# RADIO.net
KiCad netlist of a schematic drawn in EAGLE
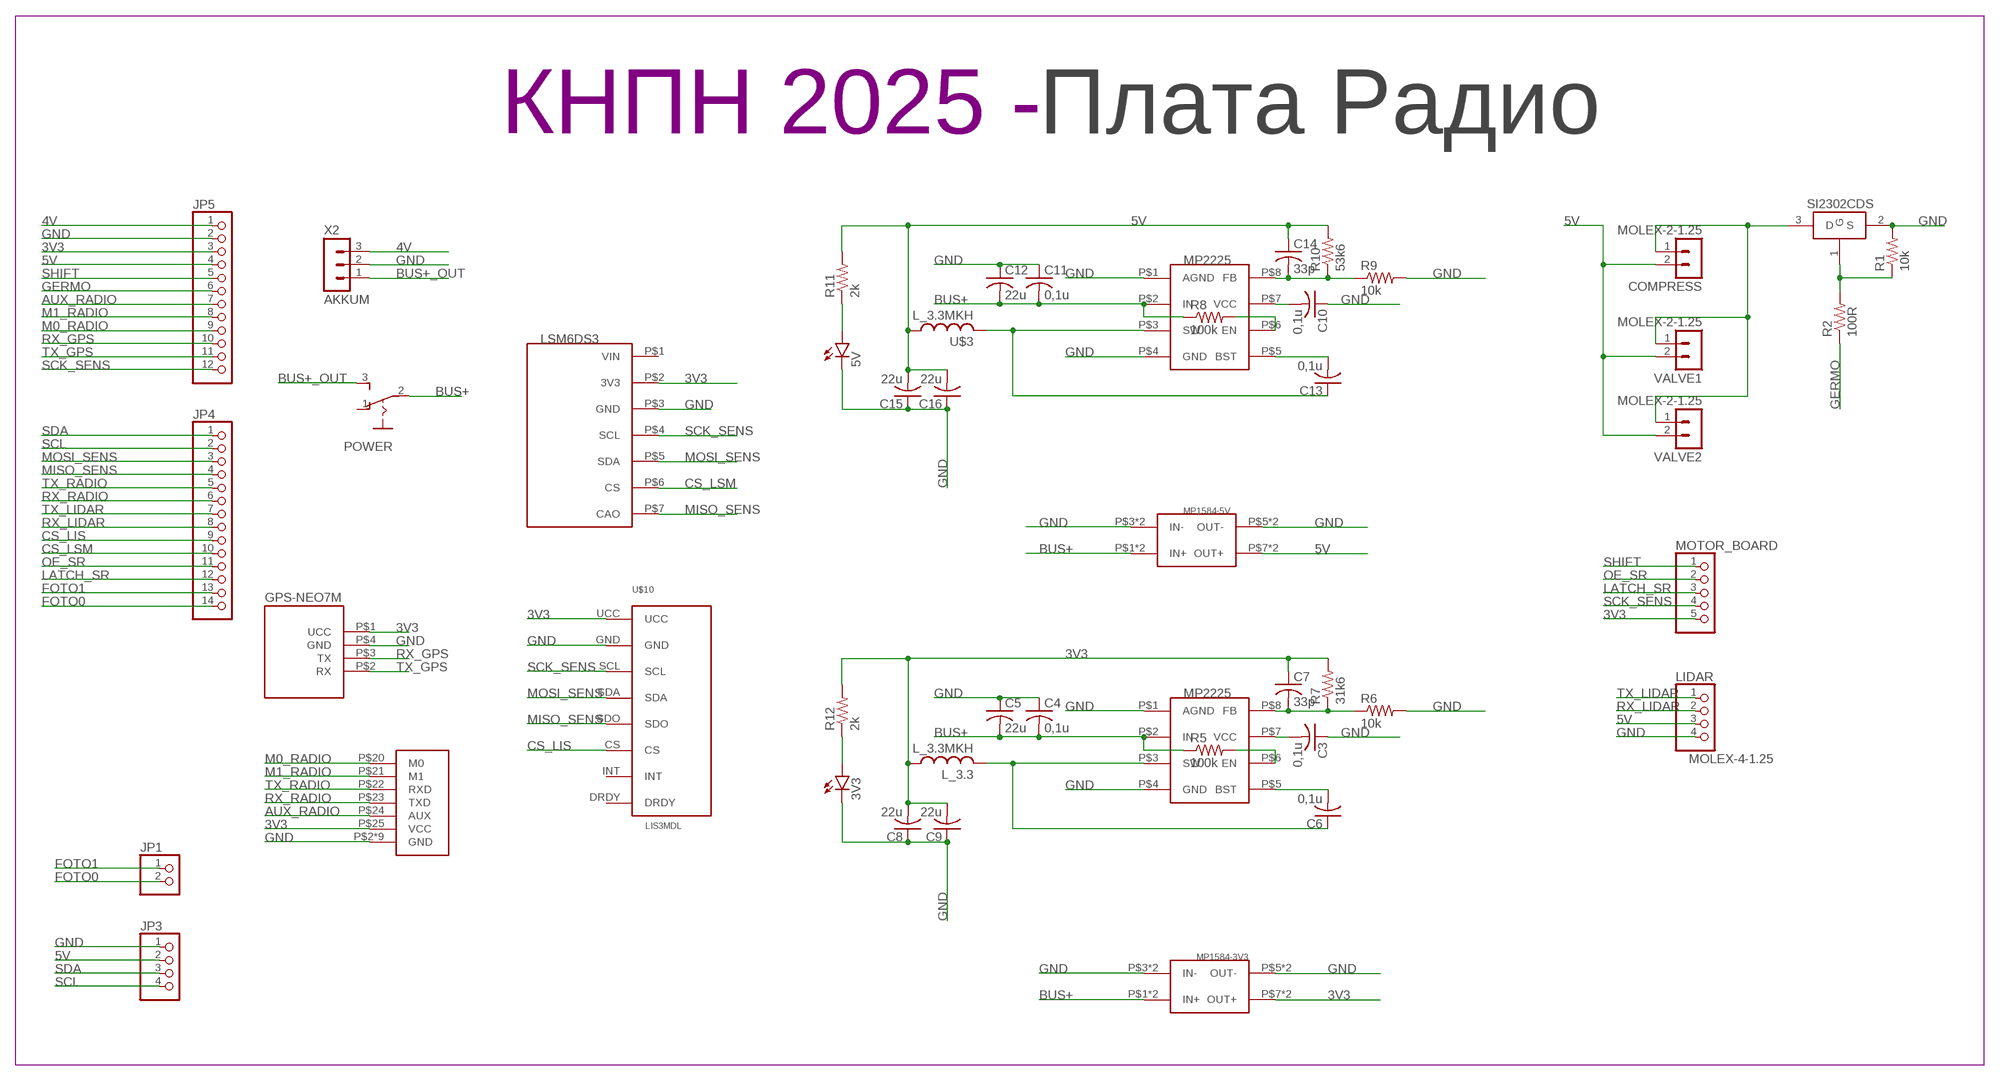
[diagram p0: schematic, sheet 1]

(export (version "E")
  (design (tool "Eeschema 10.0.6"))
  (components
    (comp (ref "3V3")
      (value "LEDCHIP-LED0603")
      (footprint "eagle-import:CHIP-LED0603")
      (libsource (lib "eagle-import") (part "LEDCHIP-LED0603"))
    )
    (comp (ref "5V")
      (value "LEDCHIP-LED0603")
      (footprint "eagle-import:CHIP-LED0603")
      (libsource (lib "eagle-import") (part "LEDCHIP-LED0603"))
    )
    (comp (ref "C3")
      (value "0,1u")
      (footprint "eagle-import:C0603")
      (libsource (lib "eagle-import") (part "C-USC0603"))
    )
    (comp (ref "C4")
      (value "0,1u")
      (footprint "eagle-import:C1206")
      (libsource (lib "eagle-import") (part "C-USC1206"))
    )
    (comp (ref "C5")
      (value "22u")
      (footprint "eagle-import:C0603")
      (libsource (lib "eagle-import") (part "C-USC0603"))
    )
    (comp (ref "C6")
      (value "0,1u")
      (footprint "eagle-import:C0603")
      (libsource (lib "eagle-import") (part "C-USC0603"))
    )
    (comp (ref "C7")
      (value "33p")
      (footprint "eagle-import:C0603")
      (libsource (lib "eagle-import") (part "C-USC0603"))
    )
    (comp (ref "C8")
      (value "22u")
      (footprint "eagle-import:C1206")
      (libsource (lib "eagle-import") (part "C-USC1206"))
    )
    (comp (ref "C9")
      (value "22u")
      (footprint "eagle-import:C1206")
      (libsource (lib "eagle-import") (part "C-USC1206"))
    )
    (comp (ref "C10")
      (value "0,1u")
      (footprint "eagle-import:C0603")
      (libsource (lib "eagle-import") (part "C-USC0603"))
    )
    (comp (ref "C11")
      (value "0,1u")
      (footprint "eagle-import:C1206")
      (libsource (lib "eagle-import") (part "C-USC1206"))
    )
    (comp (ref "C12")
      (value "22u")
      (footprint "eagle-import:C0603")
      (libsource (lib "eagle-import") (part "C-USC0603"))
    )
    (comp (ref "C13")
      (value "0,1u")
      (footprint "eagle-import:C0603")
      (libsource (lib "eagle-import") (part "C-USC0603"))
    )
    (comp (ref "C14")
      (value "33p")
      (footprint "eagle-import:C0603")
      (libsource (lib "eagle-import") (part "C-USC0603"))
    )
    (comp (ref "C15")
      (value "22u")
      (footprint "eagle-import:C1206")
      (libsource (lib "eagle-import") (part "C-USC1206"))
    )
    (comp (ref "C16")
      (value "22u")
      (footprint "eagle-import:C1206")
      (libsource (lib "eagle-import") (part "C-USC1206"))
    )
    (comp (ref "COMPRESS")
      (value "MOLEX-2-1.25")
      (footprint "eagle-import:53047-02")
      (libsource (lib "eagle-import") (part "MOLEX-2-1.25"))
    )
    (comp (ref "GPS-NEO7M")
      (value "GPS-NEO7M")
      (footprint "eagle-import:GPS-NEO7M")
      (libsource (lib "eagle-import") (part "GPS-NEO7M"))
    )
    (comp (ref "JP1")
      (value "PINHD-1X2")
      (footprint "eagle-import:1X02")
      (libsource (lib "eagle-import") (part "PINHD-1X2"))
    )
    (comp (ref "JP3")
      (value "PINHD-1X4")
      (footprint "eagle-import:1X04")
      (libsource (lib "eagle-import") (part "PINHD-1X4"))
    )
    (comp (ref "JP4")
      (value "PINHD-1X14")
      (footprint "eagle-import:1X14")
      (libsource (lib "eagle-import") (part "PINHD-1X14"))
    )
    (comp (ref "JP5")
      (value "PINHD-1X12")
      (footprint "eagle-import:1X12")
      (libsource (lib "eagle-import") (part "PINHD-1X12"))
    )
    (comp (ref "LIDAR")
      (value "MOLEX-4-1.25")
      (footprint "eagle-import:53047-04")
      (libsource (lib "eagle-import") (part "MOLEX-4-1.25"))
    )
    (comp (ref "LSM6DS3")
      (value "LSM6DS3")
      (footprint "eagle-import:LSM6DS3_WITHOUT")
      (libsource (lib "eagle-import") (part "LSM6DS3_WITHOUT"))
    )
    (comp (ref "L_3.3")
      (value "L_3.3MKH")
      (footprint "eagle-import:L_SPM5020")
      (libsource (lib "eagle-import") (part "L_3.3MKH_5X5"))
    )
    (comp (ref "MOTOR_BOARD")
      (value "MOLEX-5-1.25")
      (footprint "eagle-import:53047-05")
      (libsource (lib "eagle-import") (part "MOLEX-5-1.25"))
    )
    (comp (ref "MP1584-3V3")
      (value "MP1584-B")
      (footprint "eagle-import:MP1584-B")
      (libsource (lib "eagle-import") (part "MP1584-B"))
    )
    (comp (ref "MP1584-5V")
      (value "MP1584")
      (footprint "eagle-import:MP1584-B")
      (libsource (lib "eagle-import") (part "MP1584-B"))
    )
    (comp (ref "POWER")
      (value "UNICS-SWITCHSS_12D11")
      (footprint "eagle-import:SS_12D11")
      (libsource (lib "eagle-import") (part "UNICS-SWITCHSS_12D11"))
    )
    (comp (ref "R1")
      (value "10k")
      (footprint "eagle-import:R0603")
      (libsource (lib "eagle-import") (part "R-US_R0603"))
    )
    (comp (ref "R2")
      (value "100R")
      (footprint "eagle-import:R0603")
      (libsource (lib "eagle-import") (part "R-US_R0603"))
    )
    (comp (ref "R5")
      (value "100k")
      (footprint "eagle-import:R0603")
      (libsource (lib "eagle-import") (part "R-US_R0603"))
    )
    (comp (ref "R6")
      (value "10k")
      (footprint "eagle-import:R0603")
      (libsource (lib "eagle-import") (part "R-US_R0603"))
    )
    (comp (ref "R7")
      (value "31k6")
      (footprint "eagle-import:R0603")
      (libsource (lib "eagle-import") (part "R-US_R0603"))
    )
    (comp (ref "R8")
      (value "100k")
      (footprint "eagle-import:R0603")
      (libsource (lib "eagle-import") (part "R-US_R0603"))
    )
    (comp (ref "R9")
      (value "10k")
      (footprint "eagle-import:R0603")
      (libsource (lib "eagle-import") (part "R-US_R0603"))
    )
    (comp (ref "R10")
      (value "53k6")
      (footprint "eagle-import:R0603")
      (libsource (lib "eagle-import") (part "R-US_R0603"))
    )
    (comp (ref "R11")
      (value "2k")
      (footprint "eagle-import:R0603")
      (libsource (lib "eagle-import") (part "R-US_R0603"))
    )
    (comp (ref "R12")
      (value "2k")
      (footprint "eagle-import:R0603")
      (libsource (lib "eagle-import") (part "R-US_R0603"))
    )
    (comp (ref "RADIO")
      (value "E220-400T22S")
      (footprint "eagle-import:E220-400T22S")
      (libsource (lib "eagle-import") (part "E220-400T22S"))
    )
    (comp (ref "SI2302")
      (value "SI2302CDS")
      (footprint "eagle-import:SOT23-3")
      (libsource (lib "eagle-import") (part "SI2302CDS"))
    )
    (comp (ref "U$1")
      (value "Плата Радио")
      (footprint "eagle-import:LOGO")
      (libsource (lib "eagle-import") (part "LOGOPCB-{dblquote}{dblquote}"))
    )
    (comp (ref "U$2")
      (value "MP2225")
      (footprint "eagle-import:TSOT23-8")
      (libsource (lib "eagle-import") (part "MP2225"))
    )
    (comp (ref "U$3")
      (value "L_3.3MKH")
      (footprint "eagle-import:L_SPM5020")
      (libsource (lib "eagle-import") (part "L_3.3MKH_5X5"))
    )
    (comp (ref "U$5")
      (value "MP2225")
      (footprint "eagle-import:TSOT23-8")
      (libsource (lib "eagle-import") (part "MP2225"))
    )
    (comp (ref "U$10")
      (value "LIS3MDL")
      (footprint "eagle-import:LIS3MDL")
      (libsource (lib "eagle-import") (part "LIS3MDL"))
    )
    (comp (ref "VALVE1")
      (value "MOLEX-2-1.25")
      (footprint "eagle-import:53047-02")
      (libsource (lib "eagle-import") (part "MOLEX-2-1.25"))
    )
    (comp (ref "VALVE2")
      (value "MOLEX-2-1.25")
      (footprint "eagle-import:53047-02")
      (libsource (lib "eagle-import") (part "MOLEX-2-1.25"))
    )
    (comp (ref "X2")
      (value "AKKUM")
      (footprint "eagle-import:JST-3-2.5")
      (libsource (lib "eagle-import") (part "JST-3-2.5"))
    )
  )
  (nets
    (net (code "1") (name "/3V3") (class "Default")
      (node (ref "C7") (pin "1") (pinfunction "1_1") (pintype "passive"))
      (node (ref "C8") (pin "2") (pinfunction "2_2") (pintype "passive"))
      (node (ref "C9") (pin "2") (pinfunction "2_2") (pintype "passive"))
      (node (ref "GPS-NEO7M") (pin "P$1") (pinfunction "UCC_P$1") (pintype "bidirectional"))
      (node (ref "JP5") (pin "3") (pinfunction "3_3") (pintype "passive"))
      (node (ref "LSM6DS3") (pin "P$2") (pinfunction "3V3_P$2") (pintype "bidirectional"))
      (node (ref "L_3.3") (pin "P$1") (pinfunction "1_P$1") (pintype "passive"))
      (node (ref "MOTOR_BOARD") (pin "5") (pinfunction "5_5") (pintype "passive"))
      (node (ref "MP1584-3V3") (pin "P$7") (pinfunction "OUT+_P$7") (pintype "bidirectional"))
      (node (ref "MP1584-3V3") (pin "P$8") (pinfunction "OUT+_P$8") (pintype "bidirectional"))
      (node (ref "R12") (pin "2") (pinfunction "2_2") (pintype "passive"))
      (node (ref "R7") (pin "2") (pinfunction "2_2") (pintype "passive"))
      (node (ref "RADIO") (pin "P$25") (pinfunction "VCC_P$25") (pintype "bidirectional"))
      (node (ref "U$10") (pin "UCC") (pinfunction "UCC_UCC") (pintype "bidirectional"))
    )
    (net (code "2") (name "/4V") (class "Default")
      (node (ref "JP5") (pin "1") (pinfunction "1_1") (pintype "passive"))
      (node (ref "X2") (pin "3") (pinfunction "3_3") (pintype "passive"))
    )
    (net (code "3") (name "/5V") (class "Default")
      (node (ref "C14") (pin "1") (pinfunction "1_1") (pintype "passive"))
      (node (ref "C15") (pin "2") (pinfunction "2_2") (pintype "passive"))
      (node (ref "C16") (pin "2") (pinfunction "2_2") (pintype "passive"))
      (node (ref "COMPRESS") (pin "2") (pinfunction "2_2") (pintype "passive"))
      (node (ref "JP3") (pin "2") (pinfunction "2_2") (pintype "passive"))
      (node (ref "JP5") (pin "4") (pinfunction "4_4") (pintype "passive"))
      (node (ref "LIDAR") (pin "3") (pinfunction "3_3") (pintype "passive"))
      (node (ref "MP1584-5V") (pin "P$7") (pinfunction "OUT+_P$7") (pintype "bidirectional"))
      (node (ref "MP1584-5V") (pin "P$8") (pinfunction "OUT+_P$8") (pintype "bidirectional"))
      (node (ref "R10") (pin "2") (pinfunction "2_2") (pintype "passive"))
      (node (ref "R11") (pin "2") (pinfunction "2_2") (pintype "passive"))
      (node (ref "U$3") (pin "P$1") (pinfunction "1_P$1") (pintype "passive"))
      (node (ref "VALVE1") (pin "2") (pinfunction "2_2") (pintype "passive"))
      (node (ref "VALVE2") (pin "2") (pinfunction "2_2") (pintype "passive"))
    )
    (net (code "4") (name "/AUX_RADIO") (class "Default")
      (node (ref "JP5") (pin "7") (pinfunction "7_7") (pintype "passive"))
      (node (ref "RADIO") (pin "P$24") (pinfunction "AUX_P$24") (pintype "bidirectional"))
    )
    (net (code "5") (name "/BUS+") (class "Default")
      (node (ref "C11") (pin "2") (pinfunction "2_2") (pintype "passive"))
      (node (ref "C12") (pin "2") (pinfunction "2_2") (pintype "passive"))
      (node (ref "C4") (pin "2") (pinfunction "2_2") (pintype "passive"))
      (node (ref "C5") (pin "2") (pinfunction "2_2") (pintype "passive"))
      (node (ref "MP1584-3V3") (pin "P$1") (pinfunction "IN+_P$1") (pintype "bidirectional"))
      (node (ref "MP1584-3V3") (pin "P$2") (pinfunction "IN+_P$2") (pintype "bidirectional"))
      (node (ref "MP1584-5V") (pin "P$1") (pinfunction "IN+_P$1") (pintype "bidirectional"))
      (node (ref "MP1584-5V") (pin "P$2") (pinfunction "IN+_P$2") (pintype "bidirectional"))
      (node (ref "POWER") (pin "2") (pinfunction "P_2") (pintype "passive"))
      (node (ref "R5") (pin "1") (pinfunction "1_1") (pintype "passive"))
      (node (ref "R8") (pin "1") (pinfunction "1_1") (pintype "passive"))
      (node (ref "U$2") (pin "P$2") (pinfunction "IN_P$2") (pintype "bidirectional"))
      (node (ref "U$5") (pin "P$2") (pinfunction "IN_P$2") (pintype "bidirectional"))
    )
    (net (code "6") (name "/BUS+_OUT") (class "Default")
      (node (ref "POWER") (pin "3") (pinfunction "S_3") (pintype "passive"))
      (node (ref "X2") (pin "1") (pinfunction "1_1") (pintype "passive"))
    )
    (net (code "7") (name "/CS_LIS") (class "Default")
      (node (ref "JP4") (pin "9") (pinfunction "9_9") (pintype "passive"))
      (node (ref "U$10") (pin "CS") (pinfunction "CS_CS") (pintype "bidirectional"))
    )
    (net (code "8") (name "/CS_LSM") (class "Default")
      (node (ref "JP4") (pin "10") (pinfunction "10_10") (pintype "passive"))
      (node (ref "LSM6DS3") (pin "P$6") (pinfunction "CS_P$6") (pintype "bidirectional"))
    )
    (net (code "9") (name "/FOTO0") (class "Default")
      (node (ref "JP1") (pin "2") (pinfunction "2_2") (pintype "passive"))
      (node (ref "JP4") (pin "14") (pinfunction "14_14") (pintype "passive"))
    )
    (net (code "10") (name "/FOTO1") (class "Default")
      (node (ref "JP1") (pin "1") (pinfunction "1_1") (pintype "passive"))
      (node (ref "JP4") (pin "13") (pinfunction "13_13") (pintype "passive"))
    )
    (net (code "11") (name "/GERMO") (class "Default")
      (node (ref "JP5") (pin "6") (pinfunction "6_6") (pintype "passive"))
      (node (ref "R2") (pin "1") (pinfunction "1_1") (pintype "passive"))
    )
    (net (code "12") (name "/GND") (class "Default")
      (node (ref "3V3") (pin "C") (pinfunction "C_C") (pintype "passive"))
      (node (ref "5V") (pin "C") (pinfunction "C_C") (pintype "passive"))
      (node (ref "C10") (pin "1") (pinfunction "1_1") (pintype "passive"))
      (node (ref "C11") (pin "1") (pinfunction "1_1") (pintype "passive"))
      (node (ref "C12") (pin "1") (pinfunction "1_1") (pintype "passive"))
      (node (ref "C15") (pin "1") (pinfunction "1_1") (pintype "passive"))
      (node (ref "C16") (pin "1") (pinfunction "1_1") (pintype "passive"))
      (node (ref "C3") (pin "1") (pinfunction "1_1") (pintype "passive"))
      (node (ref "C4") (pin "1") (pinfunction "1_1") (pintype "passive"))
      (node (ref "C5") (pin "1") (pinfunction "1_1") (pintype "passive"))
      (node (ref "C8") (pin "1") (pinfunction "1_1") (pintype "passive"))
      (node (ref "C9") (pin "1") (pinfunction "1_1") (pintype "passive"))
      (node (ref "GPS-NEO7M") (pin "P$4") (pinfunction "GND_P$4") (pintype "bidirectional"))
      (node (ref "JP3") (pin "1") (pinfunction "1_1") (pintype "passive"))
      (node (ref "JP5") (pin "2") (pinfunction "2_2") (pintype "passive"))
      (node (ref "LIDAR") (pin "4") (pinfunction "4_4") (pintype "passive"))
      (node (ref "LSM6DS3") (pin "P$3") (pinfunction "GND_P$3") (pintype "bidirectional"))
      (node (ref "MP1584-3V3") (pin "P$3") (pinfunction "IN-_P$3") (pintype "bidirectional"))
      (node (ref "MP1584-3V3") (pin "P$4") (pinfunction "IN-_P$4") (pintype "bidirectional"))
      (node (ref "MP1584-3V3") (pin "P$5") (pinfunction "OUT-_P$5") (pintype "bidirectional"))
      (node (ref "MP1584-3V3") (pin "P$6") (pinfunction "OUT-_P$6") (pintype "bidirectional"))
      (node (ref "MP1584-5V") (pin "P$3") (pinfunction "IN-_P$3") (pintype "bidirectional"))
      (node (ref "MP1584-5V") (pin "P$4") (pinfunction "IN-_P$4") (pintype "bidirectional"))
      (node (ref "MP1584-5V") (pin "P$5") (pinfunction "OUT-_P$5") (pintype "bidirectional"))
      (node (ref "MP1584-5V") (pin "P$6") (pinfunction "OUT-_P$6") (pintype "bidirectional"))
      (node (ref "R1") (pin "2") (pinfunction "2_2") (pintype "passive"))
      (node (ref "R6") (pin "2") (pinfunction "2_2") (pintype "passive"))
      (node (ref "R9") (pin "2") (pinfunction "2_2") (pintype "passive"))
      (node (ref "RADIO") (pin "P$11") (pinfunction "GND_P$11") (pintype "bidirectional"))
      (node (ref "RADIO") (pin "P$13") (pinfunction "GND_P$13") (pintype "bidirectional"))
      (node (ref "RADIO") (pin "P$14") (pinfunction "GND_P$14") (pintype "bidirectional"))
      (node (ref "RADIO") (pin "P$15") (pinfunction "GND_P$15") (pintype "bidirectional"))
      (node (ref "RADIO") (pin "P$16") (pinfunction "GND_P$16") (pintype "bidirectional"))
      (node (ref "RADIO") (pin "P$19") (pinfunction "GND_P$19") (pintype "bidirectional"))
      (node (ref "RADIO") (pin "P$2") (pinfunction "GND_P$2") (pintype "bidirectional"))
      (node (ref "RADIO") (pin "P$26") (pinfunction "GND_P$26") (pintype "bidirectional"))
      (node (ref "RADIO") (pin "P$8") (pinfunction "GND_P$8") (pintype "bidirectional"))
      (node (ref "SI2302") (pin "2") (pinfunction "S_2") (pintype "bidirectional"))
      (node (ref "U$10") (pin "GND") (pinfunction "GND_GND") (pintype "bidirectional"))
      (node (ref "U$2") (pin "P$1") (pinfunction "AGND_P$1") (pintype "bidirectional"))
      (node (ref "U$2") (pin "P$4") (pinfunction "GND_P$4") (pintype "bidirectional"))
      (node (ref "U$5") (pin "P$1") (pinfunction "AGND_P$1") (pintype "bidirectional"))
      (node (ref "U$5") (pin "P$4") (pinfunction "GND_P$4") (pintype "bidirectional"))
      (node (ref "X2") (pin "2") (pinfunction "2_2") (pintype "passive"))
    )
    (net (code "13") (name "/LATCH_SR") (class "Default")
      (node (ref "JP4") (pin "12") (pinfunction "12_12") (pintype "passive"))
      (node (ref "MOTOR_BOARD") (pin "3") (pinfunction "3_3") (pintype "passive"))
    )
    (net (code "14") (name "/M0_RADIO") (class "Default")
      (node (ref "JP5") (pin "9") (pinfunction "9_9") (pintype "passive"))
      (node (ref "RADIO") (pin "P$20") (pinfunction "M0_P$20") (pintype "bidirectional"))
    )
    (net (code "15") (name "/M1_RADIO") (class "Default")
      (node (ref "JP5") (pin "8") (pinfunction "8_8") (pintype "passive"))
      (node (ref "RADIO") (pin "P$21") (pinfunction "M1_P$21") (pintype "bidirectional"))
    )
    (net (code "16") (name "/MISO_SENS") (class "Default")
      (node (ref "JP4") (pin "4") (pinfunction "4_4") (pintype "passive"))
      (node (ref "LSM6DS3") (pin "P$7") (pinfunction "CAO_P$7") (pintype "bidirectional"))
      (node (ref "U$10") (pin "SDO") (pinfunction "SDO_SDO") (pintype "bidirectional"))
    )
    (net (code "17") (name "/MOSI_SENS") (class "Default")
      (node (ref "JP4") (pin "3") (pinfunction "3_3") (pintype "passive"))
      (node (ref "LSM6DS3") (pin "P$5") (pinfunction "SDA_P$5") (pintype "bidirectional"))
      (node (ref "U$10") (pin "SDA") (pinfunction "SDA_SDA") (pintype "bidirectional"))
    )
    (net (code "18") (name "/OE_SR") (class "Default")
      (node (ref "JP4") (pin "11") (pinfunction "11_11") (pintype "passive"))
      (node (ref "MOTOR_BOARD") (pin "2") (pinfunction "2_2") (pintype "passive"))
    )
    (net (code "19") (name "/RX_GPS") (class "Default")
      (node (ref "GPS-NEO7M") (pin "P$3") (pinfunction "TX_P$3") (pintype "bidirectional"))
      (node (ref "JP5") (pin "10") (pinfunction "10_10") (pintype "passive"))
    )
    (net (code "20") (name "/RX_LIDAR") (class "Default")
      (node (ref "JP4") (pin "8") (pinfunction "8_8") (pintype "passive"))
      (node (ref "LIDAR") (pin "2") (pinfunction "2_2") (pintype "passive"))
    )
    (net (code "21") (name "/RX_RADIO") (class "Default")
      (node (ref "JP4") (pin "6") (pinfunction "6_6") (pintype "passive"))
      (node (ref "RADIO") (pin "P$23") (pinfunction "TXD_P$23") (pintype "bidirectional"))
    )
    (net (code "22") (name "/SCK_SENS") (class "Default")
      (node (ref "JP5") (pin "12") (pinfunction "12_12") (pintype "passive"))
      (node (ref "LSM6DS3") (pin "P$4") (pinfunction "SCL_P$4") (pintype "bidirectional"))
      (node (ref "MOTOR_BOARD") (pin "4") (pinfunction "4_4") (pintype "passive"))
      (node (ref "U$10") (pin "SCL") (pinfunction "SCL_SCL") (pintype "bidirectional"))
    )
    (net (code "23") (name "/SCL") (class "Default")
      (node (ref "JP3") (pin "4") (pinfunction "4_4") (pintype "passive"))
      (node (ref "JP4") (pin "2") (pinfunction "2_2") (pintype "passive"))
    )
    (net (code "24") (name "/SDA") (class "Default")
      (node (ref "JP3") (pin "3") (pinfunction "3_3") (pintype "passive"))
      (node (ref "JP4") (pin "1") (pinfunction "1_1") (pintype "passive"))
    )
    (net (code "25") (name "/SHIFT") (class "Default")
      (node (ref "JP5") (pin "5") (pinfunction "5_5") (pintype "passive"))
      (node (ref "MOTOR_BOARD") (pin "1") (pinfunction "1_1") (pintype "passive"))
    )
    (net (code "26") (name "/TX_GPS") (class "Default")
      (node (ref "GPS-NEO7M") (pin "P$2") (pinfunction "RX_P$2") (pintype "bidirectional"))
      (node (ref "JP5") (pin "11") (pinfunction "11_11") (pintype "passive"))
    )
    (net (code "27") (name "/TX_LIDAR") (class "Default")
      (node (ref "JP4") (pin "7") (pinfunction "7_7") (pintype "passive"))
      (node (ref "LIDAR") (pin "1") (pinfunction "1_1") (pintype "passive"))
    )
    (net (code "28") (name "/TX_RADIO") (class "Default")
      (node (ref "JP4") (pin "5") (pinfunction "5_5") (pintype "passive"))
      (node (ref "RADIO") (pin "P$22") (pinfunction "RXD_P$22") (pintype "bidirectional"))
    )
    (net (code "29") (name "Net-(3V3-PadA)") (class "Default")
      (node (ref "3V3") (pin "A") (pinfunction "A_A") (pintype "passive"))
      (node (ref "R12") (pin "1") (pinfunction "1_1") (pintype "passive"))
    )
    (net (code "30") (name "Net-(5V-PadA)") (class "Default")
      (node (ref "5V") (pin "A") (pinfunction "A_A") (pintype "passive"))
      (node (ref "R11") (pin "1") (pinfunction "1_1") (pintype "passive"))
    )
    (net (code "31") (name "Net-(L_3.3-2)") (class "Default")
      (node (ref "C6") (pin "1") (pinfunction "1_1") (pintype "passive"))
      (node (ref "L_3.3") (pin "P$2") (pinfunction "2_P$2") (pintype "passive"))
      (node (ref "U$2") (pin "P$3") (pinfunction "SW_P$3") (pintype "bidirectional"))
    )
    (net (code "32") (name "Net-(SI2302-D)") (class "Default")
      (node (ref "COMPRESS") (pin "1") (pinfunction "1_1") (pintype "passive"))
      (node (ref "SI2302") (pin "3") (pinfunction "D_3") (pintype "bidirectional"))
      (node (ref "VALVE1") (pin "1") (pinfunction "1_1") (pintype "passive"))
      (node (ref "VALVE2") (pin "1") (pinfunction "1_1") (pintype "passive"))
    )
    (net (code "33") (name "Net-(SI2302-G)") (class "Default")
      (node (ref "R1") (pin "1") (pinfunction "1_1") (pintype "passive"))
      (node (ref "R2") (pin "2") (pinfunction "2_2") (pintype "passive"))
      (node (ref "SI2302") (pin "1") (pinfunction "G_1") (pintype "bidirectional"))
    )
    (net (code "34") (name "Net-(U$2-BST)") (class "Default")
      (node (ref "C6") (pin "2") (pinfunction "2_2") (pintype "passive"))
      (node (ref "U$2") (pin "P$5") (pinfunction "BST_P$5") (pintype "bidirectional"))
    )
    (net (code "35") (name "Net-(U$2-EN)") (class "Default")
      (node (ref "R5") (pin "2") (pinfunction "2_2") (pintype "passive"))
      (node (ref "U$2") (pin "P$6") (pinfunction "EN_P$6") (pintype "bidirectional"))
    )
    (net (code "36") (name "Net-(U$2-FB)") (class "Default")
      (node (ref "C7") (pin "2") (pinfunction "2_2") (pintype "passive"))
      (node (ref "R6") (pin "1") (pinfunction "1_1") (pintype "passive"))
      (node (ref "R7") (pin "1") (pinfunction "1_1") (pintype "passive"))
      (node (ref "U$2") (pin "P$8") (pinfunction "FB_P$8") (pintype "bidirectional"))
    )
    (net (code "37") (name "Net-(U$2-VCC)") (class "Default")
      (node (ref "C3") (pin "2") (pinfunction "2_2") (pintype "passive"))
      (node (ref "U$2") (pin "P$7") (pinfunction "VCC_P$7") (pintype "bidirectional"))
    )
    (net (code "38") (name "Net-(U$3-2)") (class "Default")
      (node (ref "C13") (pin "1") (pinfunction "1_1") (pintype "passive"))
      (node (ref "U$3") (pin "P$2") (pinfunction "2_P$2") (pintype "passive"))
      (node (ref "U$5") (pin "P$3") (pinfunction "SW_P$3") (pintype "bidirectional"))
    )
    (net (code "39") (name "Net-(U$5-BST)") (class "Default")
      (node (ref "C13") (pin "2") (pinfunction "2_2") (pintype "passive"))
      (node (ref "U$5") (pin "P$5") (pinfunction "BST_P$5") (pintype "bidirectional"))
    )
    (net (code "40") (name "Net-(U$5-EN)") (class "Default")
      (node (ref "R8") (pin "2") (pinfunction "2_2") (pintype "passive"))
      (node (ref "U$5") (pin "P$6") (pinfunction "EN_P$6") (pintype "bidirectional"))
    )
    (net (code "41") (name "Net-(U$5-FB)") (class "Default")
      (node (ref "C14") (pin "2") (pinfunction "2_2") (pintype "passive"))
      (node (ref "R10") (pin "1") (pinfunction "1_1") (pintype "passive"))
      (node (ref "R9") (pin "1") (pinfunction "1_1") (pintype "passive"))
      (node (ref "U$5") (pin "P$8") (pinfunction "FB_P$8") (pintype "bidirectional"))
    )
    (net (code "42") (name "Net-(U$5-VCC)") (class "Default")
      (node (ref "C10") (pin "2") (pinfunction "2_2") (pintype "passive"))
      (node (ref "U$5") (pin "P$7") (pinfunction "VCC_P$7") (pintype "bidirectional"))
    )
    (net (code "43") (name "unconnected-(LSM6DS3-VIN-PadP$1)") (class "Default")
      (node (ref "LSM6DS3") (pin "P$1") (pinfunction "VIN_P$1") (pintype "bidirectional"))
    )
    (net (code "44") (name "unconnected-(POWER-O-Pad1)") (class "Default")
      (node (ref "POWER") (pin "1") (pinfunction "O_1") (pintype "passive"))
    )
    (net (code "45") (name "unconnected-(U$10-PadDRDY)") (class "Default")
      (node (ref "U$10") (pin "DRDY") (pinfunction "DRDY_DRDY") (pintype "bidirectional"))
    )
    (net (code "46") (name "unconnected-(U$10-PadINT)") (class "Default")
      (node (ref "U$10") (pin "INT") (pinfunction "INT_INT") (pintype "bidirectional"))
    )
  )
)
